# Motor-X.net
KiCad netlist of a schematic drawn in Altium Designer
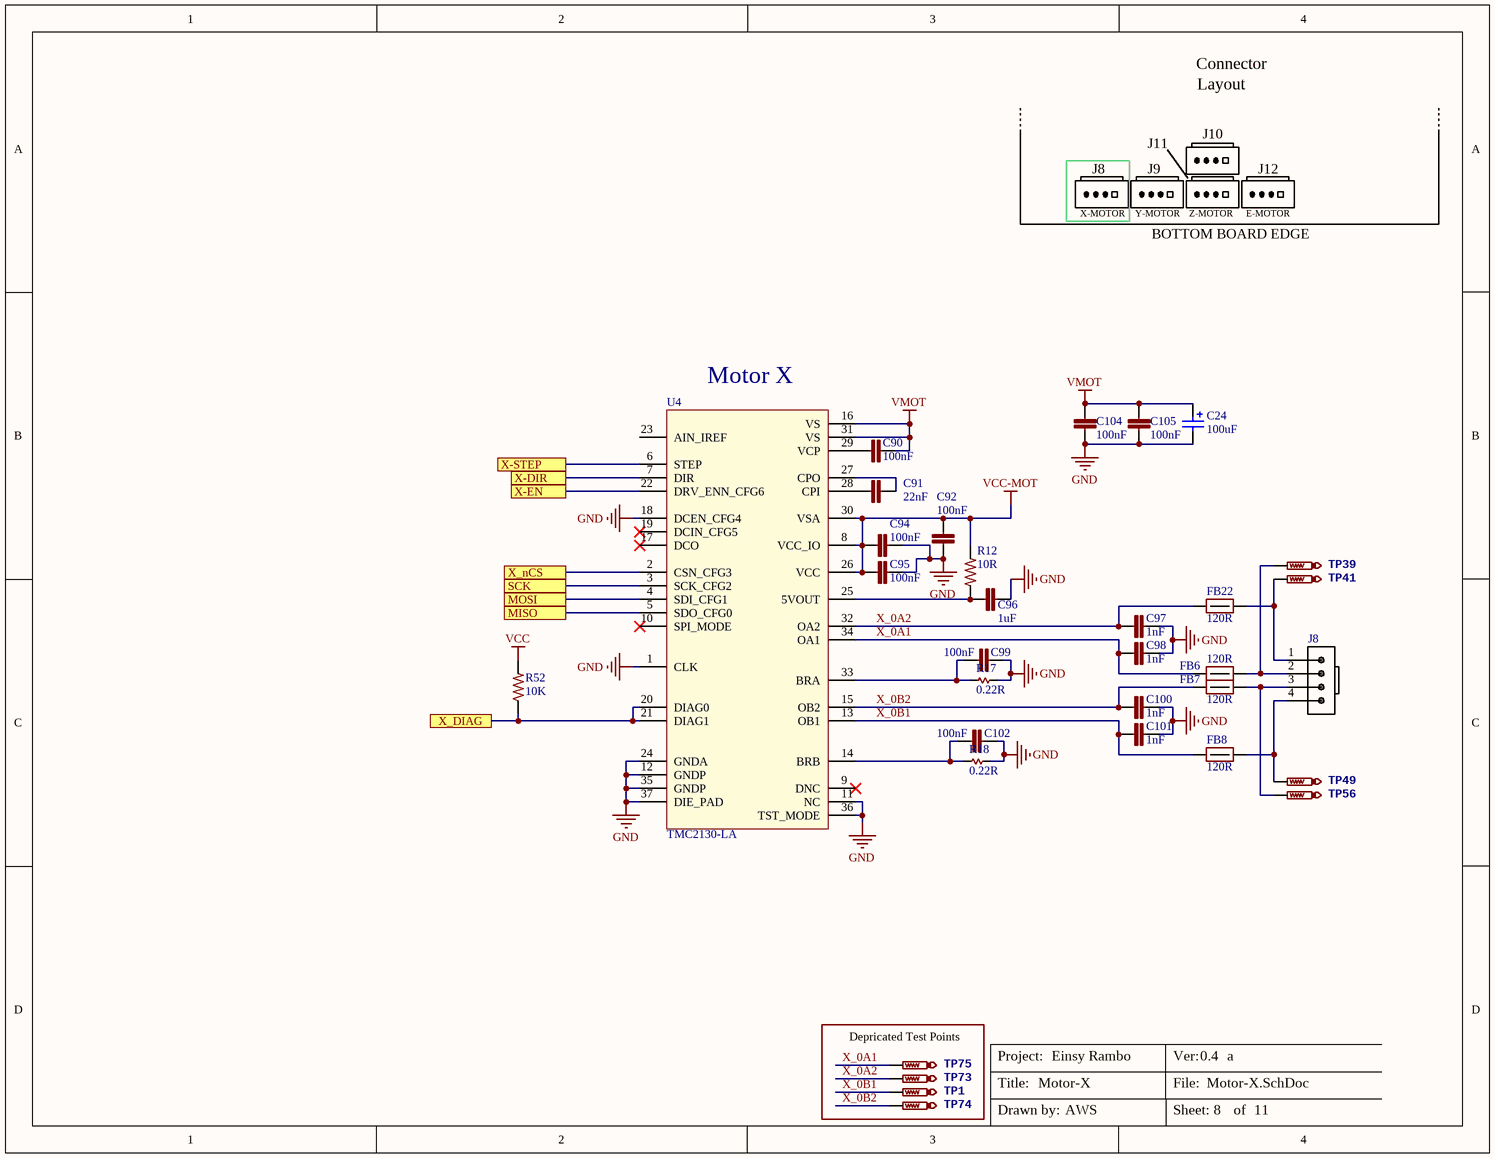
[diagram p0: Motor-X.SchDoc]

(export (version "E")
  (design (tool "Eeschema 10.0.6"))
  (components
    (comp (ref "C24")
      (value "100uF")
      (footprint "CAP-ELEC-063063077")
      (description "CAP ALUM 100UF 35V 20% SMD")
      (fields (field (name "MANUFACTURER") "Nichicon") (field (name "TOLERANCE") "+/- 20%"))
      (libsource (lib "3Delight") (part "UWT1V101MCL1GS"))
    )
    (comp (ref "C90")
      (value "100nF")
      (footprint "C0603")
      (description "CAP CER 0603 100nF 50V 10% X7R")
      (fields (field (name "MANUFACTURER") "Kemet") (field (name "TOLERANCE") "+/- 10%"))
      (libsource (lib "") (part "C0603C104K5RACTU_1"))
    )
    (comp (ref "C91")
      (value "22nF")
      (footprint "C0402")
      (description "CAP CER 0402 22nF ±10% 50V X7R")
      (fields (field (name "MANUFACTURER") "YAGEO") (field (name "TOLERANCE") "+/- 10%"))
      (libsource (lib "3Delight") (part "GCM155R71H223KA55D"))
    )
    (comp (ref "C92")
      (value "100nF")
      (footprint "C0402")
      (description "CAP CER 0402 100nF 16V 10% X7R")
      (fields (field (name "MANUFACTURER") "Murata") (field (name "TOLERANCE") "+/- 10%"))
      (libsource (lib "") (part "GRM155R71C104KA88D_1"))
    )
    (comp (ref "C94")
      (value "100nF")
      (footprint "C0402")
      (description "CAP CER 0402 100nF 16V 10% X7R")
      (fields (field (name "MANUFACTURER") "Murata") (field (name "TOLERANCE") "+/- 10%"))
      (libsource (lib "3Delight") (part "GRM155R71C104KA88D"))
    )
    (comp (ref "C95")
      (value "100nF")
      (footprint "C0402")
      (description "CAP CER 0402 100nF 16V 10% X7R")
      (fields (field (name "MANUFACTURER") "Murata") (field (name "TOLERANCE") "+/- 10%"))
      (libsource (lib "3Delight") (part "GRM155R71C104KA88D"))
    )
    (comp (ref "C96")
      (value "1uF")
      (footprint "C0402")
      (description "CAP CER 0402 1uF 6.3V 10% X5R")
      (fields (field (name "MANUFACTURER") "Murata") (field (name "TOLERANCE") "+/- 10%"))
      (libsource (lib "3Delight") (part "GRM155R60J105KE19D"))
    )
    (comp (ref "C97")
      (value "1nF")
      (footprint "C0603")
      (description "CAP CER 0603  1nF 50v 10% X7R")
      (fields (field (name "MANUFACTURER") "Kemet") (field (name "TOLERANCE") "+/- 10%"))
      (libsource (lib "3Delight") (part "C0603C102K5RACTU"))
    )
    (comp (ref "C98")
      (value "1nF")
      (footprint "C0603")
      (description "CAP CER 0603  1nF 50v 10% X7R")
      (fields (field (name "MANUFACTURER") "Kemet") (field (name "TOLERANCE") "+/- 10%"))
      (libsource (lib "3Delight") (part "C0603C102K5RACTU"))
    )
    (comp (ref "C99")
      (value "100nF")
      (footprint "C0603")
      (description "CAP CER 0603 100nF 50V 10% X7R")
      (fields (field (name "MANUFACTURER") "Kemet") (field (name "TOLERANCE") "+/- 10%"))
      (libsource (lib "3Delight") (part "C0603C104K5RACTU"))
    )
    (comp (ref "C100")
      (value "1nF")
      (footprint "C0603")
      (description "CAP CER 0603  1nF 50v 10% X7R")
      (fields (field (name "MANUFACTURER") "Kemet") (field (name "TOLERANCE") "+/- 10%"))
      (libsource (lib "3Delight") (part "C0603C102K5RACTU"))
    )
    (comp (ref "C101")
      (value "1nF")
      (footprint "C0603")
      (description "CAP CER 0603  1nF 50v 10% X7R")
      (fields (field (name "MANUFACTURER") "Kemet") (field (name "TOLERANCE") "+/- 10%"))
      (libsource (lib "3Delight") (part "C0603C102K5RACTU"))
    )
    (comp (ref "C102")
      (value "100nF")
      (footprint "C0603")
      (description "CAP CER 0603 100nF 50V 10% X7R")
      (fields (field (name "MANUFACTURER") "Kemet") (field (name "TOLERANCE") "+/- 10%"))
      (libsource (lib "3Delight") (part "C0603C104K5RACTU"))
    )
    (comp (ref "C104")
      (value "100nF")
      (footprint "C0603")
      (description "CAP CER 0603 100nF 50V 10% X7R")
      (fields (field (name "MANUFACTURER") "Kemet") (field (name "TOLERANCE") "+/- 10%"))
      (libsource (lib "") (part "C0603C104K5RACTU_2"))
    )
    (comp (ref "C105")
      (value "100nF")
      (footprint "C0603")
      (description "CAP CER 0603 100nF 50V 10% X7R")
      (fields (field (name "MANUFACTURER") "Kemet") (field (name "TOLERANCE") "+/- 10%"))
      (libsource (lib "") (part "C0603C104K5RACTU_2"))
    )
    (comp (ref "FB6")
      (value "120R")
      (footprint "FB0603")
      (description "FERRITE BEAD 120 OHM 0603 1LN")
      (fields (field (name "MANUFACTURER") "Samsung") (field (name "PART") "FERRITE 120R 3A 0603"))
      (libsource (lib "Inductors") (part "FERRITE 120R 3A 0603"))
    )
    (comp (ref "FB7")
      (value "120R")
      (footprint "FB0603")
      (description "FERRITE BEAD 120 OHM 0603 1LN")
      (fields (field (name "MANUFACTURER") "Samsung") (field (name "PART") "FERRITE 120R 3A 0603"))
      (libsource (lib "Inductors") (part "FERRITE 120R 3A 0603"))
    )
    (comp (ref "FB8")
      (value "120R")
      (footprint "FB0603")
      (description "FERRITE BEAD 120 OHM 0603 1LN")
      (fields (field (name "MANUFACTURER") "Samsung") (field (name "PART") "FERRITE 120R 3A 0603"))
      (libsource (lib "Inductors") (part "FERRITE 120R 3A 0603"))
    )
    (comp (ref "FB22")
      (value "120R")
      (footprint "FB0603")
      (description "FERRITE BEAD 120 OHM 0603 1LN")
      (fields (field (name "MANUFACTURER") "Samsung") (field (name "PART") "FERRITE 120R 3A 0603"))
      (libsource (lib "Inductors") (part "FERRITE 120R 3A 0603"))
    )
    (comp (ref "J8")
      (value "Molex 0705430003")
      (footprint "4POL254 PIN-IN-PASTE")
      (description "Molex 4 Pin Clip Connector")
      (libsource (lib "Connectors") (part "Molex 0705430003 PIN-IN-PASTE"))
    )
    (comp (ref "R12")
      (value "10R")
      (footprint "R0402")
      (description "RES SMD 10 OHM 1% 1/16W 0402")
      (fields (field (name "MANUFACTURER") "Yageo") (field (name "TOLERANCE") "+/- 1%"))
      (libsource (lib "3Delight") (part "RC0402FR-0710RL"))
    )
    (comp (ref "R17")
      (value "0.22R")
      (footprint "R1206")
      (description "RES SMD 0.22 OHM 1% 1/3W 1206")
      (fields (field (name "MANUFACTURER") "Panasonic") (field (name "TOLERANCE") "+/- 1%"))
      (libsource (lib "Resistors") (part "0.22R 1% 1206"))
    )
    (comp (ref "R18")
      (value "0.22R")
      (footprint "R1206")
      (description "RES SMD 0.22 OHM 1% 1/3W 1206")
      (fields (field (name "MANUFACTURER") "Panasonic") (field (name "TOLERANCE") "+/- 1%"))
      (libsource (lib "Resistors") (part "0.22R 1% 1206"))
    )
    (comp (ref "R52")
      (value "10K")
      (footprint "R0402")
      (description "RES SMD 10K OHM 1% 1/16W 0402")
      (fields (field (name "MANUFACTURER") "Yageo") (field (name "PART") "10k 1% 0402"))
      (libsource (lib "3Delight") (part "RC0402FR-0710KP"))
    )
    (comp (ref "TP1")
      (value "TestPoint")
      (footprint "TP1-27")
      (description "Test Point")
      (libsource (lib "3Delight") (part "TestPoint"))
    )
    (comp (ref "TP39")
      (value "TestPoint")
      (footprint "TP1-27")
      (description "Test Point")
      (libsource (lib "3Delight") (part "TestPoint"))
    )
    (comp (ref "TP41")
      (value "TestPoint")
      (footprint "TP1-27")
      (description "Test Point")
      (libsource (lib "3Delight") (part "TestPoint"))
    )
    (comp (ref "TP49")
      (value "TestPoint")
      (footprint "TP1-27")
      (description "Test Point")
      (libsource (lib "3Delight") (part "TestPoint"))
    )
    (comp (ref "TP56")
      (value "TestPoint")
      (footprint "TP1-27")
      (description "Test Point")
      (libsource (lib "3Delight") (part "TestPoint"))
    )
    (comp (ref "TP73")
      (value "TestPoint")
      (footprint "TP1-27")
      (description "Test Point")
      (libsource (lib "3Delight") (part "TestPoint"))
    )
    (comp (ref "TP74")
      (value "TestPoint")
      (footprint "TP1-27")
      (description "Test Point")
      (libsource (lib "3Delight") (part "TestPoint"))
    )
    (comp (ref "TP75")
      (value "TestPoint")
      (footprint "TP1-27")
      (description "Test Point")
      (libsource (lib "3Delight") (part "TestPoint"))
    )
    (comp (ref "U4")
      (value "TMC2130-LA")
      (footprint "QFN36-DualSolderMask")
      (description "IC STEPPER MOTOR DVR SPI 36QFN")
      (fields (field (name "MANUFACTURER") "Trinamic") (field (name "PART") "TMC2130"))
      (libsource (lib "ICs-Motor Controller") (part "TMC2130-DualSolderMask"))
    )
  )
  (nets
    (net (code "1") (name "/MISO") (class "Default")
      (node (ref "U4") (pin "5") (pinfunction "SDO_CFG0_5") (pintype "passive"))
    )
    (net (code "2") (name "/MOSI") (class "Default")
      (node (ref "U4") (pin "4") (pinfunction "SDI_CFG1_4") (pintype "passive"))
    )
    (net (code "3") (name "/SCK") (class "Default")
      (node (ref "U4") (pin "3") (pinfunction "SCK_CFG2_3") (pintype "passive"))
    )
    (net (code "4") (name "/X-DIR") (class "Default")
      (node (ref "U4") (pin "7") (pinfunction "DIR_7") (pintype "passive"))
    )
    (net (code "5") (name "/X-EN") (class "Default")
      (node (ref "U4") (pin "22") (pinfunction "DRV_ENN_CFG6_22") (pintype "passive"))
    )
    (net (code "6") (name "/X-STEP") (class "Default")
      (node (ref "U4") (pin "6") (pinfunction "STEP_6") (pintype "passive"))
    )
    (net (code "7") (name "/X_0A1") (class "Default")
      (node (ref "C98") (pin "1") (pinfunction "1_1") (pintype "passive"))
      (node (ref "FB6") (pin "1") (pinfunction "1_1") (pintype "passive"))
      (node (ref "TP75") (pin "TP") (pinfunction "TP_TP") (pintype "passive"))
      (node (ref "U4") (pin "34") (pinfunction "OA1_34") (pintype "passive"))
    )
    (net (code "8") (name "/X_0A2") (class "Default")
      (node (ref "C97") (pin "1") (pinfunction "1_1") (pintype "passive"))
      (node (ref "FB22") (pin "1") (pinfunction "1_1") (pintype "passive"))
      (node (ref "TP73") (pin "TP") (pinfunction "TP_TP") (pintype "passive"))
      (node (ref "U4") (pin "32") (pinfunction "OA2_32") (pintype "passive"))
    )
    (net (code "9") (name "/X_0B1") (class "Default")
      (node (ref "C101") (pin "1") (pinfunction "1_1") (pintype "passive"))
      (node (ref "FB8") (pin "1") (pinfunction "1_1") (pintype "passive"))
      (node (ref "TP1") (pin "TP") (pinfunction "TP_TP") (pintype "passive"))
      (node (ref "U4") (pin "13") (pinfunction "OB1_13") (pintype "passive"))
    )
    (net (code "10") (name "/X_0B2") (class "Default")
      (node (ref "C100") (pin "1") (pinfunction "1_1") (pintype "passive"))
      (node (ref "FB7") (pin "1") (pinfunction "1_1") (pintype "passive"))
      (node (ref "TP74") (pin "TP") (pinfunction "TP_TP") (pintype "passive"))
      (node (ref "U4") (pin "15") (pinfunction "OB2_15") (pintype "passive"))
    )
    (net (code "11") (name "/X_DIAG") (class "Default")
      (node (ref "R52") (pin "1") (pinfunction "1_1") (pintype "passive"))
      (node (ref "U4") (pin "20") (pinfunction "DIAG0_20") (pintype "passive"))
      (node (ref "U4") (pin "21") (pinfunction "DIAG1_21") (pintype "passive"))
    )
    (net (code "12") (name "/X_nCS") (class "Default")
      (node (ref "U4") (pin "2") (pinfunction "CSN_CFG3_2") (pintype "passive"))
    )
    (net (code "13") (name "GND") (class "Default")
      (node (ref "C100") (pin "2") (pinfunction "2_2") (pintype "passive"))
      (node (ref "C101") (pin "2") (pinfunction "2_2") (pintype "passive"))
      (node (ref "C102") (pin "1") (pinfunction "1_1") (pintype "passive"))
      (node (ref "C104") (pin "1") (pinfunction "1_1") (pintype "passive"))
      (node (ref "C105") (pin "1") (pinfunction "1_1") (pintype "passive"))
      (node (ref "C24") (pin "2") (pinfunction "2_2") (pintype "passive"))
      (node (ref "C92") (pin "1") (pinfunction "1_1") (pintype "passive"))
      (node (ref "C94") (pin "1") (pinfunction "1_1") (pintype "passive"))
      (node (ref "C95") (pin "1") (pinfunction "1_1") (pintype "passive"))
      (node (ref "C96") (pin "2") (pinfunction "2_2") (pintype "passive"))
      (node (ref "C97") (pin "2") (pinfunction "2_2") (pintype "passive"))
      (node (ref "C98") (pin "2") (pinfunction "2_2") (pintype "passive"))
      (node (ref "C99") (pin "1") (pinfunction "1_1") (pintype "passive"))
      (node (ref "R17") (pin "2") (pinfunction "2_2") (pintype "passive"))
      (node (ref "R18") (pin "2") (pinfunction "2_2") (pintype "passive"))
      (node (ref "U4") (pin "1") (pinfunction "CLK_1") (pintype "passive"))
      (node (ref "U4") (pin "11") (pinfunction "NC_11") (pintype "passive"))
      (node (ref "U4") (pin "12") (pinfunction "GNDP_12") (pintype "passive"))
      (node (ref "U4") (pin "18") (pinfunction "DCEN_CFG4_18") (pintype "passive"))
      (node (ref "U4") (pin "24") (pinfunction "GNDA_24") (pintype "passive"))
      (node (ref "U4") (pin "35") (pinfunction "GNDP_35") (pintype "passive"))
      (node (ref "U4") (pin "36") (pinfunction "TST_MODE_36") (pintype "passive"))
      (node (ref "U4") (pin "37") (pinfunction "DIE_PAD_37") (pintype "passive"))
    )
    (net (code "14") (name "Net-(FB6-Pad2)") (class "Default")
      (node (ref "FB6") (pin "2") (pinfunction "2_2") (pintype "passive"))
      (node (ref "J8") (pin "2") (pinfunction "2_2") (pintype "passive"))
      (node (ref "TP39") (pin "TP") (pinfunction "TP_TP") (pintype "passive"))
    )
    (net (code "15") (name "Net-(FB7-Pad2)") (class "Default")
      (node (ref "FB7") (pin "2") (pinfunction "2_2") (pintype "passive"))
      (node (ref "J8") (pin "3") (pinfunction "3_3") (pintype "passive"))
      (node (ref "TP56") (pin "TP") (pinfunction "TP_TP") (pintype "passive"))
    )
    (net (code "16") (name "Net-(FB8-Pad2)") (class "Default")
      (node (ref "FB8") (pin "2") (pinfunction "2_2") (pintype "passive"))
      (node (ref "J8") (pin "4") (pinfunction "4_4") (pintype "passive"))
      (node (ref "TP49") (pin "TP") (pinfunction "TP_TP") (pintype "passive"))
    )
    (net (code "17") (name "Net-(FB22-Pad2)") (class "Default")
      (node (ref "FB22") (pin "2") (pinfunction "2_2") (pintype "passive"))
      (node (ref "J8") (pin "1") (pinfunction "1_1") (pintype "passive"))
      (node (ref "TP41") (pin "TP") (pinfunction "TP_TP") (pintype "passive"))
    )
    (net (code "18") (name "Net-(U4-5VOUT)") (class "Default")
      (node (ref "C96") (pin "1") (pinfunction "1_1") (pintype "passive"))
      (node (ref "R12") (pin "1") (pinfunction "1_1") (pintype "passive"))
      (node (ref "U4") (pin "25") (pinfunction "5VOUT_25") (pintype "passive"))
    )
    (net (code "19") (name "Net-(U4-BRA)") (class "Default")
      (node (ref "C99") (pin "2") (pinfunction "2_2") (pintype "passive"))
      (node (ref "R17") (pin "1") (pinfunction "1_1") (pintype "passive"))
      (node (ref "U4") (pin "33") (pinfunction "BRA_33") (pintype "passive"))
    )
    (net (code "20") (name "Net-(U4-BRB)") (class "Default")
      (node (ref "C102") (pin "2") (pinfunction "2_2") (pintype "passive"))
      (node (ref "R18") (pin "1") (pinfunction "1_1") (pintype "passive"))
      (node (ref "U4") (pin "14") (pinfunction "BRB_14") (pintype "passive"))
    )
    (net (code "21") (name "Net-(U4-CPI)") (class "Default")
      (node (ref "C91") (pin "1") (pinfunction "1_1") (pintype "passive"))
      (node (ref "U4") (pin "28") (pinfunction "CPI_28") (pintype "passive"))
    )
    (net (code "22") (name "Net-(U4-CPO)") (class "Default")
      (node (ref "C91") (pin "2") (pinfunction "2_2") (pintype "passive"))
      (node (ref "U4") (pin "27") (pinfunction "CPO_27") (pintype "passive"))
    )
    (net (code "23") (name "Net-(U4-VCP)") (class "Default")
      (node (ref "C90") (pin "1") (pinfunction "1_1") (pintype "passive"))
      (node (ref "U4") (pin "29") (pinfunction "VCP_29") (pintype "passive"))
    )
    (net (code "24") (name "VCC") (class "Default")
      (node (ref "R52") (pin "2") (pinfunction "2_2") (pintype "passive"))
    )
    (net (code "25") (name "VCC-MOT") (class "Default")
      (node (ref "C92") (pin "2") (pinfunction "2_2") (pintype "passive"))
      (node (ref "C94") (pin "2") (pinfunction "2_2") (pintype "passive"))
      (node (ref "C95") (pin "2") (pinfunction "2_2") (pintype "passive"))
      (node (ref "R12") (pin "2") (pinfunction "2_2") (pintype "passive"))
      (node (ref "U4") (pin "26") (pinfunction "VCC_26") (pintype "passive"))
      (node (ref "U4") (pin "30") (pinfunction "VSA_30") (pintype "passive"))
      (node (ref "U4") (pin "8") (pinfunction "VCC_IO_8") (pintype "passive"))
    )
    (net (code "26") (name "VMOT") (class "Default")
      (node (ref "C104") (pin "2") (pinfunction "2_2") (pintype "passive"))
      (node (ref "C105") (pin "2") (pinfunction "2_2") (pintype "passive"))
      (node (ref "C24") (pin "1") (pinfunction "1_1") (pintype "passive"))
      (node (ref "C90") (pin "2") (pinfunction "2_2") (pintype "passive"))
      (node (ref "U4") (pin "16") (pinfunction "VS_16") (pintype "passive"))
      (node (ref "U4") (pin "31") (pinfunction "VS_31") (pintype "passive"))
    )
    (net (code "27") (name "unconnected-(U4-AIN_IREF-Pad23)") (class "Default")
      (node (ref "U4") (pin "23") (pinfunction "AIN_IREF_23") (pintype "passive"))
    )
    (net (code "28") (name "unconnected-(U4-DCIN_CFG5-Pad19)") (class "Default")
      (node (ref "U4") (pin "19") (pinfunction "DCIN_CFG5_19") (pintype "passive+no_connect"))
    )
    (net (code "29") (name "unconnected-(U4-DCO-Pad17)") (class "Default")
      (node (ref "U4") (pin "17") (pinfunction "DCO_17") (pintype "passive+no_connect"))
    )
    (net (code "30") (name "unconnected-(U4-DNC-Pad9)") (class "Default")
      (node (ref "U4") (pin "9") (pinfunction "DNC_9") (pintype "passive+no_connect"))
    )
    (net (code "31") (name "unconnected-(U4-SPI_MODE-Pad10)") (class "Default")
      (node (ref "U4") (pin "10") (pinfunction "SPI_MODE_10") (pintype "passive+no_connect"))
    )
  )
)
